# usbhub.net
KiCad netlist of a schematic drawn in EasyEDA Pro
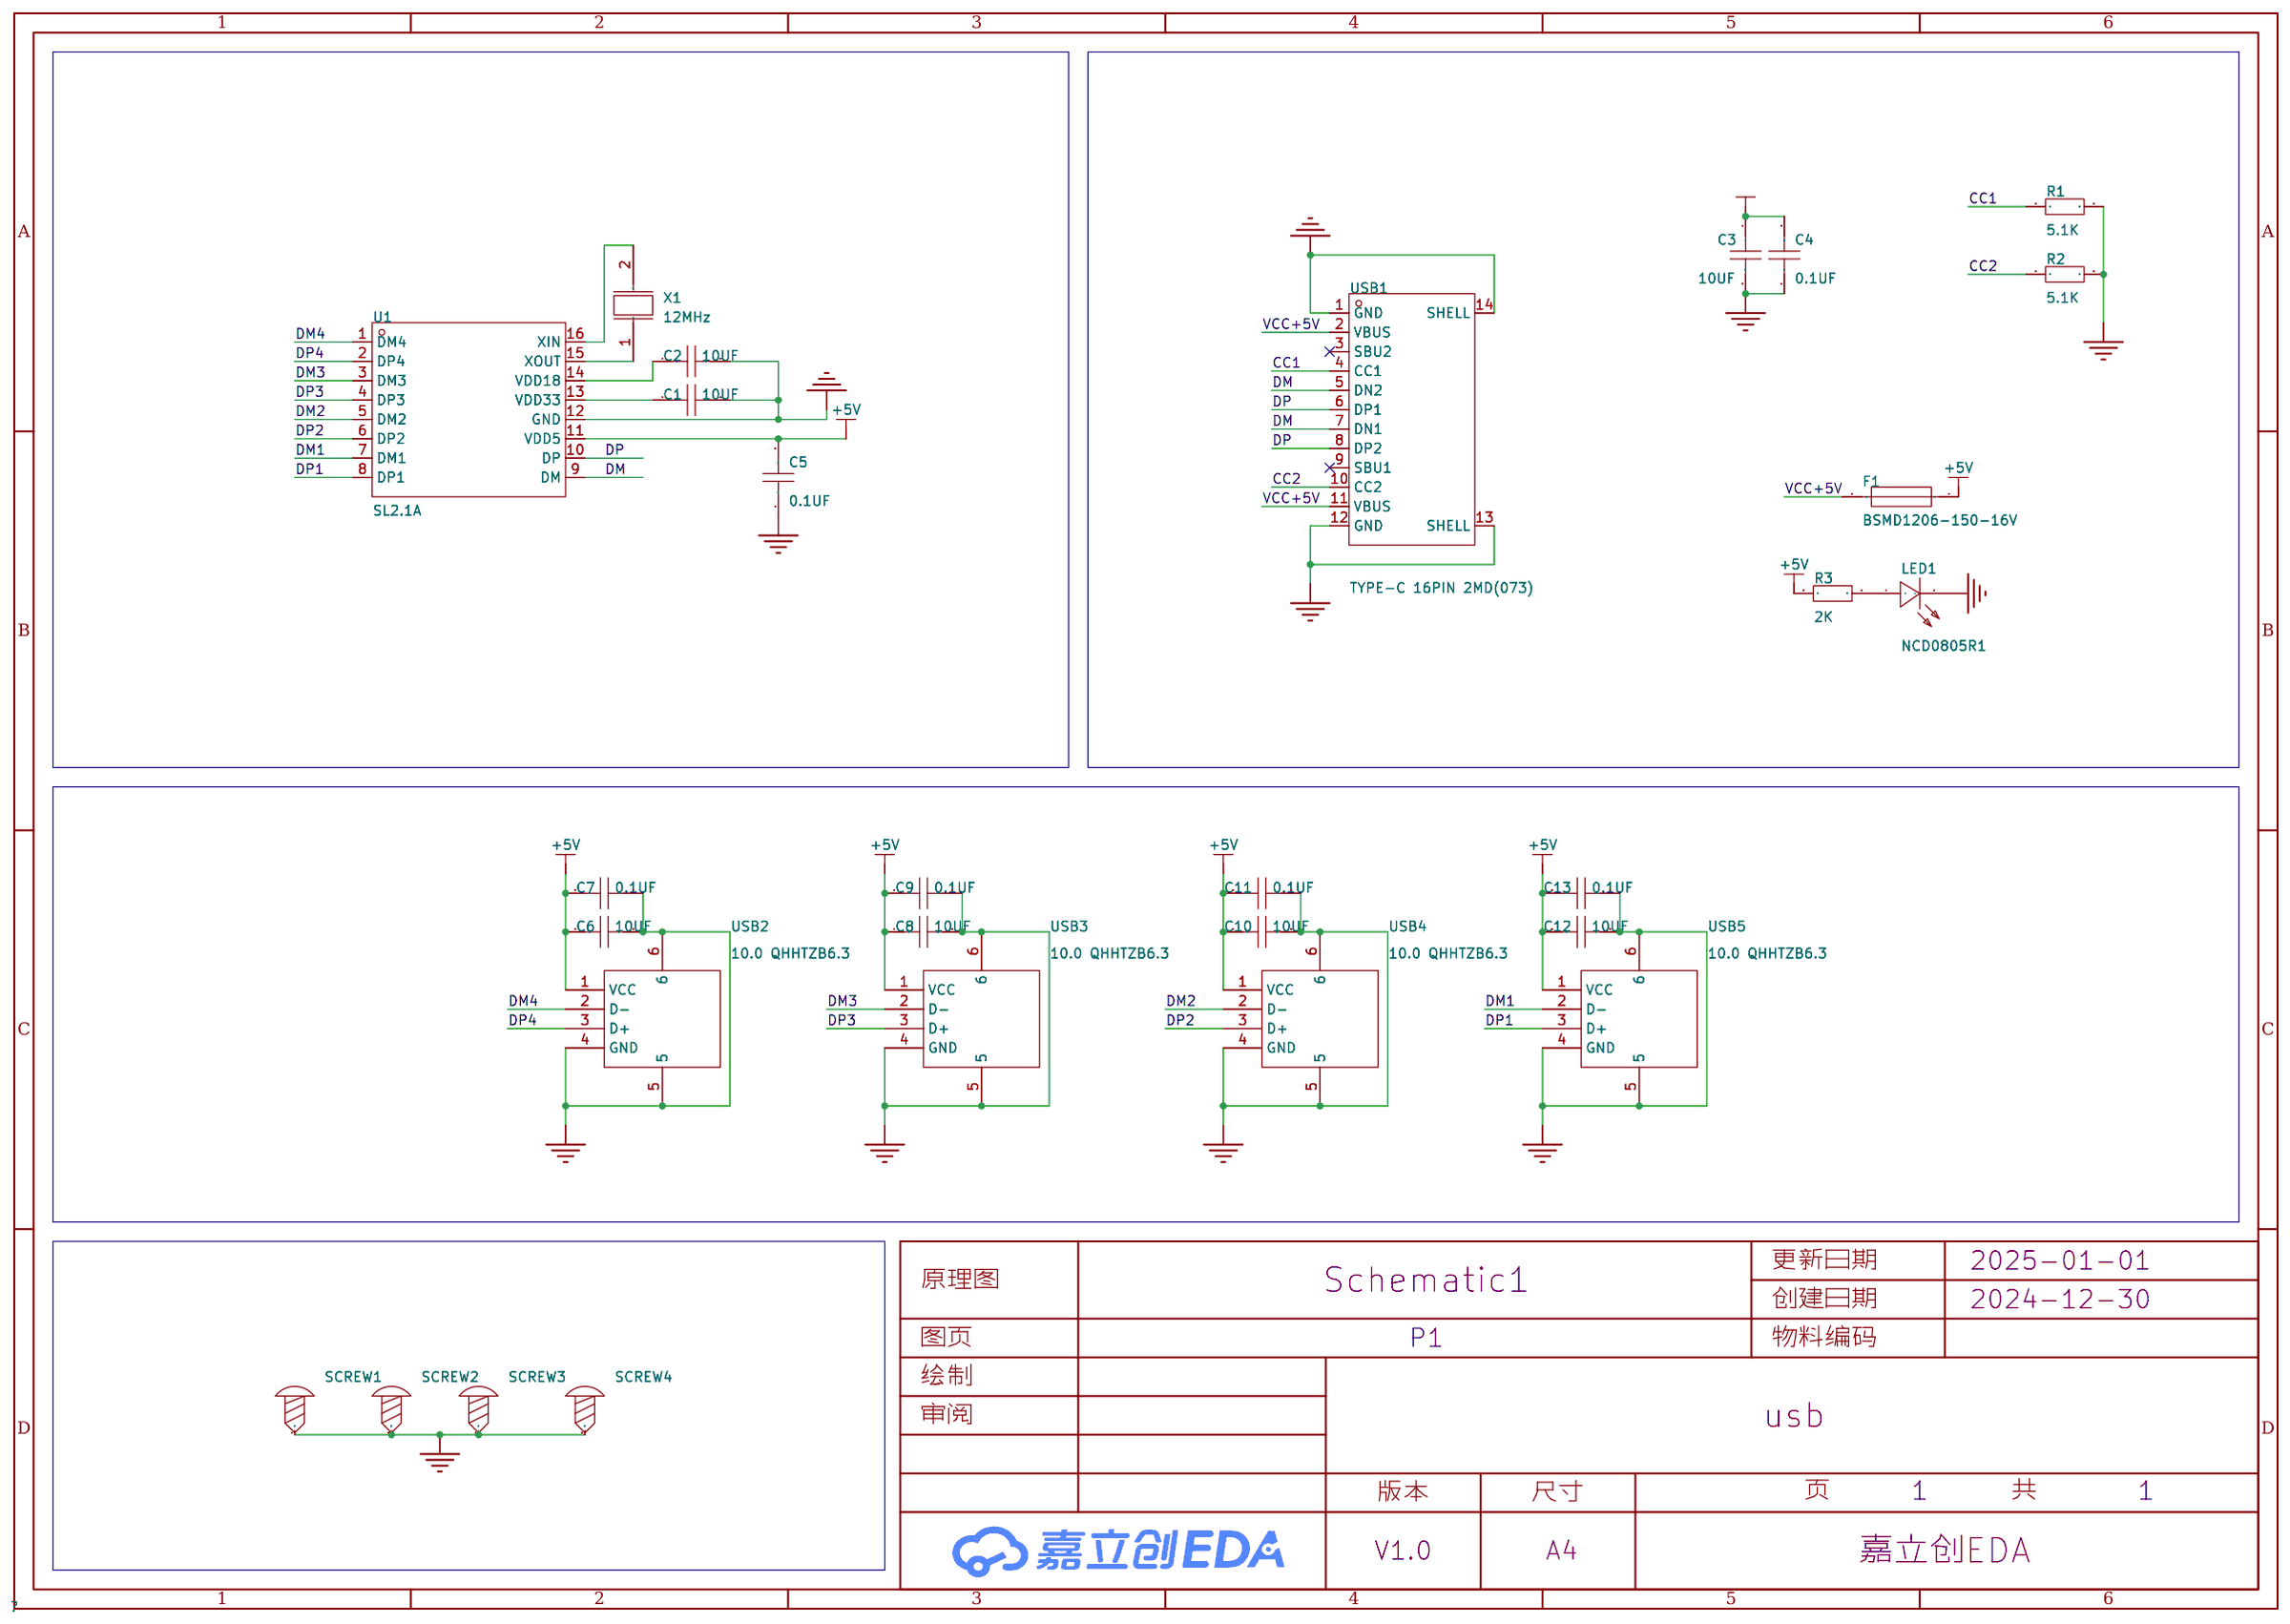
[diagram p0: schematic sheet]

(export (version "E")
  (design (tool "Eeschema 10.0.6"))
  (components
    (comp (ref "C1")
      (value "10UF")
      (footprint "easyedapro:C0805")
      (libsource (lib "easyedapro") (part "CapAcitance"))
    )
    (comp (ref "C2")
      (value "10UF")
      (footprint "easyedapro:C0805")
      (libsource (lib "easyedapro") (part "CapAcitance"))
    )
    (comp (ref "C3")
      (value "10UF")
      (footprint "easyedapro:C0805")
      (libsource (lib "easyedapro") (part "CapAcitance"))
    )
    (comp (ref "C4")
      (value "0.1UF")
      (footprint "easyedapro:C0805")
      (libsource (lib "easyedapro") (part "CapAcitance"))
    )
    (comp (ref "C5")
      (value "0.1UF")
      (footprint "easyedapro:C0805")
      (libsource (lib "easyedapro") (part "CapAcitance"))
    )
    (comp (ref "C6")
      (value "10UF")
      (footprint "easyedapro:C0805")
      (libsource (lib "easyedapro") (part "CapAcitance"))
    )
    (comp (ref "C7")
      (value "0.1UF")
      (footprint "easyedapro:C0805")
      (libsource (lib "easyedapro") (part "CapAcitance"))
    )
    (comp (ref "C8")
      (value "10UF")
      (footprint "easyedapro:C0805")
      (libsource (lib "easyedapro") (part "CapAcitance"))
    )
    (comp (ref "C9")
      (value "0.1UF")
      (footprint "easyedapro:C0805")
      (libsource (lib "easyedapro") (part "CapAcitance"))
    )
    (comp (ref "C10")
      (value "10UF")
      (footprint "easyedapro:C0805")
      (libsource (lib "easyedapro") (part "CapAcitance"))
    )
    (comp (ref "C11")
      (value "0.1UF")
      (footprint "easyedapro:C0805")
      (libsource (lib "easyedapro") (part "CapAcitance"))
    )
    (comp (ref "C12")
      (value "10UF")
      (footprint "easyedapro:C0805")
      (libsource (lib "easyedapro") (part "CapAcitance"))
    )
    (comp (ref "C13")
      (value "0.1UF")
      (footprint "easyedapro:C0805")
      (libsource (lib "easyedapro") (part "CapAcitance"))
    )
    (comp (ref "F1")
      (value "BSMD1206-150-16V")
      (footprint "easyedapro:F1206")
      (description "最大电压:16V;最大电流:40A;保持电流:1.5A;跳闸电流:3A;")
      (fields (field (name "Manufacturer") "BHFUSE(佰宏)"))
      (libsource (lib "easyedapro") (part "BSMD1206-150-16V"))
    )
    (comp (ref "LED1")
      (value "NCD0805R1")
      (footprint "easyedapro:LED0805-R-RD")
      (fields (field (name "Manufacturer") "国星光电"))
      (libsource (lib "easyedapro") (part "FC-2012HRK-620D"))
    )
    (comp (ref "R1") (value "5.1K") (footprint "easyedapro:R0805") (libsource (lib "easyedapro") (part "电阻")))
    (comp (ref "R2") (value "5.1K") (footprint "easyedapro:R0805") (libsource (lib "easyedapro") (part "电阻")))
    (comp (ref "R3") (value "2K") (footprint "easyedapro:R0805") (libsource (lib "easyedapro") (part "电阻")))
    (comp (ref "SCREW1")
      (value "~")
      (footprint "easyedapro:M2螺丝")
      (libsource (lib "easyedapro") (part "螺丝孔"))
    )
    (comp (ref "SCREW2")
      (value "~")
      (footprint "easyedapro:M2螺丝")
      (libsource (lib "easyedapro") (part "螺丝孔"))
    )
    (comp (ref "SCREW3")
      (value "~")
      (footprint "easyedapro:M2螺丝")
      (libsource (lib "easyedapro") (part "螺丝孔"))
    )
    (comp (ref "SCREW4")
      (value "~")
      (footprint "easyedapro:M2螺丝")
      (libsource (lib "easyedapro") (part "螺丝孔"))
    )
    (comp (ref "U1")
      (value "SL2.1A")
      (footprint "easyedapro:SOP-16_L10.0-W3.9-P1.27-LS6.0-BL")
      (description "SL2.1A是一颗高集成度,高性能,低功耗的USB2.0集线器主控芯片，支持USB2.0高速(480MHz),全速(12MHz)和低速模式(1.5MHz)，内置12MHz晶体振荡器。")
      (fields (field (name "Manufacturer") "CoreChips(和芯润德)"))
      (libsource (lib "easyedapro") (part "SL2.1A"))
    )
    (comp (ref "USB1")
      (value "TYPE-C 16PIN 2MD(073)")
      (footprint "easyedapro:USB-C-SMD_TYPE-C-6PIN-2MD-073")
      (description "连接器类型:Type-C;标准:USB 3.1;公母:母;安装方式:卧贴;触点数量:16P;端口数量:1;额定电流 - 电源:5A;工作温度范围:-25°C~+85°C;")
      (fields (field (name "Manufacturer") "SHOU HAN(首韩)"))
      (libsource (lib "easyedapro") (part "TYPE-C 16PIN 2MD(073)"))
    )
    (comp (ref "USB2")
      (value "10.0 QHHTZB6.3")
      (footprint "easyedapro:USB-A-TH_10.0QHHTZB6.3")
      (description "连接器类型:Type-A;标准:USB 2.0;公母:母;安装方式:卧贴;触点数量:4P;端口数量:1;额定电流 - 电源:1.5A;工作温度范围:-25°C~+85°C;")
      (fields (field (name "Manufacturer") "SHOU HAN(首韩)"))
      (libsource (lib "easyedapro") (part "10.0 QHHTZB6.3"))
    )
    (comp (ref "USB3")
      (value "10.0 QHHTZB6.3")
      (footprint "easyedapro:USB-A-TH_10.0QHHTZB6.3")
      (description "连接器类型:Type-A;标准:USB 2.0;公母:母;安装方式:卧贴;触点数量:4P;端口数量:1;额定电流 - 电源:1.5A;工作温度范围:-25°C~+85°C;")
      (fields (field (name "Manufacturer") "SHOU HAN(首韩)"))
      (libsource (lib "easyedapro") (part "10.0 QHHTZB6.3"))
    )
    (comp (ref "USB4")
      (value "10.0 QHHTZB6.3")
      (footprint "easyedapro:USB-A-TH_10.0QHHTZB6.3")
      (description "连接器类型:Type-A;标准:USB 2.0;公母:母;安装方式:卧贴;触点数量:4P;端口数量:1;额定电流 - 电源:1.5A;工作温度范围:-25°C~+85°C;")
      (fields (field (name "Manufacturer") "SHOU HAN(首韩)"))
      (libsource (lib "easyedapro") (part "10.0 QHHTZB6.3"))
    )
    (comp (ref "USB5")
      (value "10.0 QHHTZB6.3")
      (footprint "easyedapro:USB-A-TH_10.0QHHTZB6.3")
      (description "连接器类型:Type-A;标准:USB 2.0;公母:母;安装方式:卧贴;触点数量:4P;端口数量:1;额定电流 - 电源:1.5A;工作温度范围:-25°C~+85°C;")
      (fields (field (name "Manufacturer") "SHOU HAN(首韩)"))
      (libsource (lib "easyedapro") (part "10.0 QHHTZB6.3"))
    )
    (comp (ref "X1")
      (value "12MHz")
      (footprint "easyedapro:CRYSTAL-SMD_L5.0-W3.2-1-A")
      (description "晶振类型:贴片晶振;频率:12MHz;常温频差:±20ppm;外接负载电容:20pF;")
      (fields (field (name "Manufacturer Part") "G5312000202090") (field (name "Manufacturer") "JGHC(晶光华)"))
      (libsource (lib "easyedapro") (part "G5312000202090"))
    )
  )
  (nets
    (net (code "1") (name "+5V") (class "Default")
      (node (ref "C10") (pin "1") (pinfunction "1_1") (pintype "input"))
      (node (ref "C11") (pin "2") (pinfunction "2_2") (pintype "input"))
      (node (ref "C12") (pin "1") (pinfunction "1_1") (pintype "input"))
      (node (ref "C13") (pin "2") (pinfunction "2_2") (pintype "input"))
      (node (ref "C5") (pin "2") (pinfunction "2_2") (pintype "input"))
      (node (ref "C6") (pin "1") (pinfunction "1_1") (pintype "input"))
      (node (ref "C7") (pin "2") (pinfunction "2_2") (pintype "input"))
      (node (ref "C8") (pin "1") (pinfunction "1_1") (pintype "input"))
      (node (ref "C9") (pin "2") (pinfunction "2_2") (pintype "input"))
      (node (ref "F1") (pin "2") (pinfunction "2_2") (pintype "unspecified"))
      (node (ref "R3") (pin "2") (pinfunction "2_2") (pintype "input"))
      (node (ref "U1") (pin "11") (pinfunction "VDD5_11") (pintype "unspecified"))
      (node (ref "USB2") (pin "1") (pinfunction "VCC_1") (pintype "unspecified"))
      (node (ref "USB3") (pin "1") (pinfunction "VCC_1") (pintype "unspecified"))
      (node (ref "USB4") (pin "1") (pinfunction "VCC_1") (pintype "unspecified"))
      (node (ref "USB5") (pin "1") (pinfunction "VCC_1") (pintype "unspecified"))
    )
    (net (code "2") (name "/CC1") (class "Default")
      (node (ref "R1") (pin "1") (pinfunction "1_1") (pintype "input"))
      (node (ref "USB1") (pin "4") (pinfunction "CC1_4") (pintype "unspecified"))
    )
    (net (code "3") (name "/CC2") (class "Default")
      (node (ref "R2") (pin "1") (pinfunction "1_1") (pintype "input"))
      (node (ref "USB1") (pin "10") (pinfunction "CC2_10") (pintype "unspecified"))
    )
    (net (code "4") (name "/DM") (class "Default")
      (node (ref "U1") (pin "9") (pinfunction "DM_9") (pintype "unspecified"))
      (node (ref "USB1") (pin "5") (pinfunction "DN2_5") (pintype "unspecified"))
      (node (ref "USB1") (pin "7") (pinfunction "DN1_7") (pintype "unspecified"))
    )
    (net (code "5") (name "/DM1") (class "Default")
      (node (ref "U1") (pin "7") (pinfunction "DM1_7") (pintype "unspecified"))
      (node (ref "USB5") (pin "2") (pinfunction "D-_2") (pintype "unspecified"))
    )
    (net (code "6") (name "/DM2") (class "Default")
      (node (ref "U1") (pin "5") (pinfunction "DM2_5") (pintype "unspecified"))
      (node (ref "USB4") (pin "2") (pinfunction "D-_2") (pintype "unspecified"))
    )
    (net (code "7") (name "/DM3") (class "Default")
      (node (ref "U1") (pin "3") (pinfunction "DM3_3") (pintype "unspecified"))
      (node (ref "USB3") (pin "2") (pinfunction "D-_2") (pintype "unspecified"))
    )
    (net (code "8") (name "/DM4") (class "Default")
      (node (ref "U1") (pin "1") (pinfunction "DM4_1") (pintype "unspecified"))
      (node (ref "USB2") (pin "2") (pinfunction "D-_2") (pintype "unspecified"))
    )
    (net (code "9") (name "/DP") (class "Default")
      (node (ref "U1") (pin "10") (pinfunction "DP_10") (pintype "unspecified"))
      (node (ref "USB1") (pin "6") (pinfunction "DP1_6") (pintype "unspecified"))
      (node (ref "USB1") (pin "8") (pinfunction "DP2_8") (pintype "unspecified"))
    )
    (net (code "10") (name "/DP1") (class "Default")
      (node (ref "U1") (pin "8") (pinfunction "DP1_8") (pintype "unspecified"))
      (node (ref "USB5") (pin "3") (pinfunction "D+_3") (pintype "unspecified"))
    )
    (net (code "11") (name "/DP2") (class "Default")
      (node (ref "U1") (pin "6") (pinfunction "DP2_6") (pintype "unspecified"))
      (node (ref "USB4") (pin "3") (pinfunction "D+_3") (pintype "unspecified"))
    )
    (net (code "12") (name "/DP3") (class "Default")
      (node (ref "U1") (pin "4") (pinfunction "DP3_4") (pintype "unspecified"))
      (node (ref "USB3") (pin "3") (pinfunction "D+_3") (pintype "unspecified"))
    )
    (net (code "13") (name "/DP4") (class "Default")
      (node (ref "U1") (pin "2") (pinfunction "DP4_2") (pintype "unspecified"))
      (node (ref "USB2") (pin "3") (pinfunction "D+_3") (pintype "unspecified"))
    )
    (net (code "14") (name "GND") (class "Default")
      (node (ref "C1") (pin "2") (pinfunction "2_2") (pintype "input"))
      (node (ref "C10") (pin "2") (pinfunction "2_2") (pintype "input"))
      (node (ref "C11") (pin "1") (pinfunction "1_1") (pintype "input"))
      (node (ref "C12") (pin "2") (pinfunction "2_2") (pintype "input"))
      (node (ref "C13") (pin "1") (pinfunction "1_1") (pintype "input"))
      (node (ref "C2") (pin "2") (pinfunction "2_2") (pintype "input"))
      (node (ref "C3") (pin "2") (pinfunction "2_2") (pintype "input"))
      (node (ref "C4") (pin "1") (pinfunction "1_1") (pintype "input"))
      (node (ref "C5") (pin "1") (pinfunction "1_1") (pintype "input"))
      (node (ref "C6") (pin "2") (pinfunction "2_2") (pintype "input"))
      (node (ref "C7") (pin "1") (pinfunction "1_1") (pintype "input"))
      (node (ref "C8") (pin "2") (pinfunction "2_2") (pintype "input"))
      (node (ref "C9") (pin "1") (pinfunction "1_1") (pintype "input"))
      (node (ref "LED1") (pin "2") (pinfunction "-_2") (pintype "unspecified"))
      (node (ref "R1") (pin "2") (pinfunction "2_2") (pintype "input"))
      (node (ref "R2") (pin "2") (pinfunction "2_2") (pintype "input"))
      (node (ref "SCREW1") (pin "1") (pinfunction "1_1") (pintype "input"))
      (node (ref "SCREW2") (pin "1") (pinfunction "1_1") (pintype "input"))
      (node (ref "SCREW3") (pin "1") (pinfunction "1_1") (pintype "input"))
      (node (ref "SCREW4") (pin "1") (pinfunction "1_1") (pintype "input"))
      (node (ref "U1") (pin "12") (pinfunction "GND_12") (pintype "unspecified"))
      (node (ref "USB1") (pin "1") (pinfunction "GND_1") (pintype "unspecified"))
      (node (ref "USB1") (pin "12") (pinfunction "GND_12") (pintype "unspecified"))
      (node (ref "USB1") (pin "13") (pinfunction "SHELL_13") (pintype "unspecified"))
      (node (ref "USB1") (pin "14") (pinfunction "SHELL_14") (pintype "unspecified"))
      (node (ref "USB2") (pin "4") (pinfunction "GND_4") (pintype "unspecified"))
      (node (ref "USB2") (pin "5") (pinfunction "5_5") (pintype "unspecified"))
      (node (ref "USB2") (pin "6") (pinfunction "6_6") (pintype "unspecified"))
      (node (ref "USB3") (pin "4") (pinfunction "GND_4") (pintype "unspecified"))
      (node (ref "USB3") (pin "5") (pinfunction "5_5") (pintype "unspecified"))
      (node (ref "USB3") (pin "6") (pinfunction "6_6") (pintype "unspecified"))
      (node (ref "USB4") (pin "4") (pinfunction "GND_4") (pintype "unspecified"))
      (node (ref "USB4") (pin "5") (pinfunction "5_5") (pintype "unspecified"))
      (node (ref "USB4") (pin "6") (pinfunction "6_6") (pintype "unspecified"))
      (node (ref "USB5") (pin "4") (pinfunction "GND_4") (pintype "unspecified"))
      (node (ref "USB5") (pin "5") (pinfunction "5_5") (pintype "unspecified"))
      (node (ref "USB5") (pin "6") (pinfunction "6_6") (pintype "unspecified"))
    )
    (net (code "15") (name "Net-(LED1-+)") (class "Default")
      (node (ref "LED1") (pin "1") (pinfunction "+_1") (pintype "unspecified"))
      (node (ref "R3") (pin "1") (pinfunction "1_1") (pintype "input"))
    )
    (net (code "16") (name "Net-(U1-VDD18)") (class "Default")
      (node (ref "C2") (pin "1") (pinfunction "1_1") (pintype "input"))
      (node (ref "U1") (pin "14") (pinfunction "VDD18_14") (pintype "unspecified"))
    )
    (net (code "17") (name "Net-(U1-VDD33)") (class "Default")
      (node (ref "C1") (pin "1") (pinfunction "1_1") (pintype "input"))
      (node (ref "U1") (pin "13") (pinfunction "VDD33_13") (pintype "unspecified"))
    )
    (net (code "18") (name "Net-(U1-XIN)") (class "Default")
      (node (ref "U1") (pin "16") (pinfunction "XIN_16") (pintype "unspecified"))
      (node (ref "X1") (pin "2") (pinfunction "2_2") (pintype "unspecified"))
    )
    (net (code "19") (name "Net-(U1-XOUT)") (class "Default")
      (node (ref "U1") (pin "15") (pinfunction "XOUT_15") (pintype "unspecified"))
      (node (ref "X1") (pin "1") (pinfunction "1_1") (pintype "unspecified"))
    )
    (net (code "20") (name "VCC+5V") (class "Default")
      (node (ref "C3") (pin "1") (pinfunction "1_1") (pintype "input"))
      (node (ref "C4") (pin "2") (pinfunction "2_2") (pintype "input"))
      (node (ref "F1") (pin "1") (pinfunction "1_1") (pintype "unspecified"))
      (node (ref "USB1") (pin "11") (pinfunction "VBUS_11") (pintype "unspecified"))
      (node (ref "USB1") (pin "2") (pinfunction "VBUS_2") (pintype "unspecified"))
    )
    (net (code "21") (name "unconnected-(USB1-SBU1-Pad9)") (class "Default")
      (node (ref "USB1") (pin "9") (pinfunction "SBU1_9") (pintype "unspecified+no_connect"))
    )
    (net (code "22") (name "unconnected-(USB1-SBU2-Pad3)") (class "Default")
      (node (ref "USB1") (pin "3") (pinfunction "SBU2_3") (pintype "unspecified+no_connect"))
    )
  )
)
